# Dual_linear_VCA_chip_v1_1.net
KiCad netlist of a schematic drawn in EAGLE
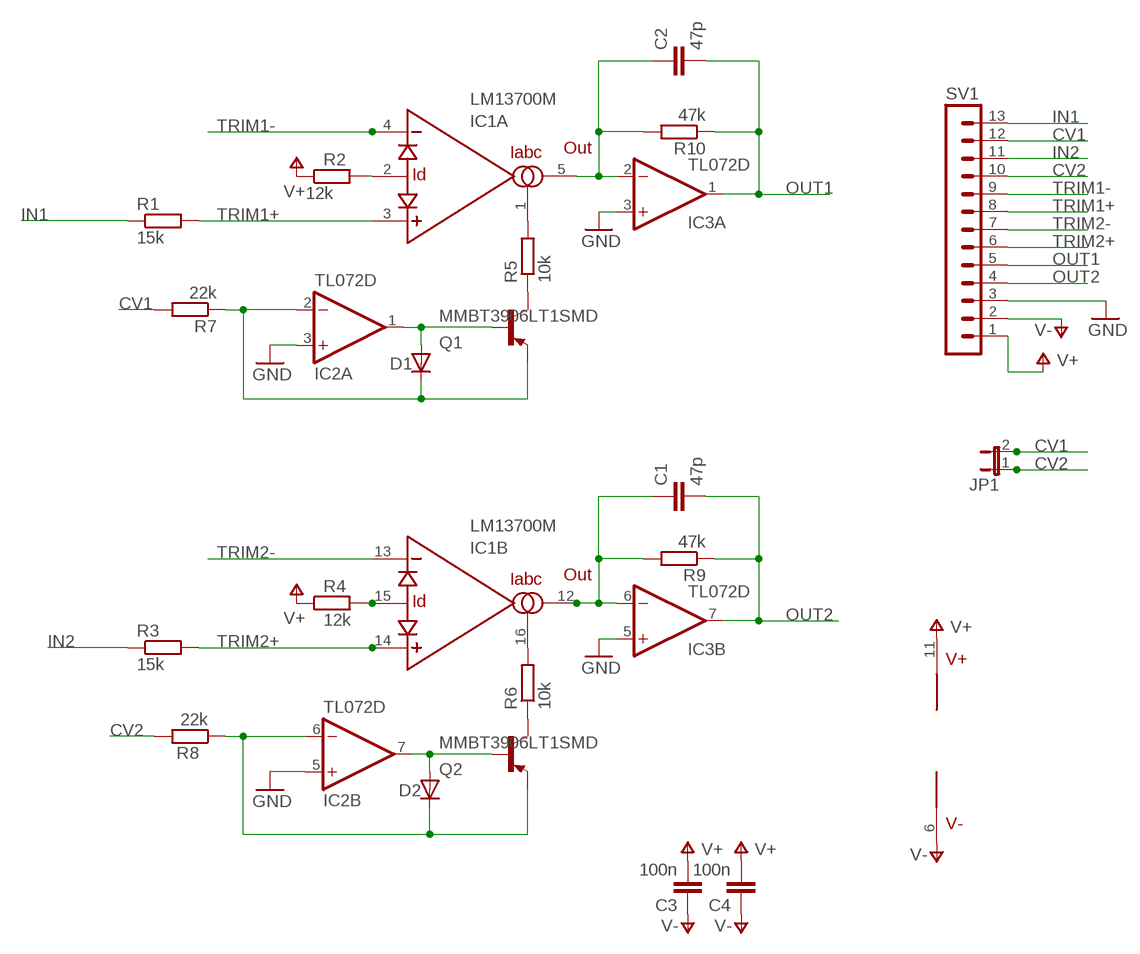
[diagram p0: schematic, sheet 1]

(export (version "E")
  (design (tool "Eeschema 10.0.6"))
  (components
    (comp (ref "C1")
      (value "47p")
      (footprint "eagle-import:C0805")
      (libsource (lib "eagle-import") (part "C-EUC0805"))
    )
    (comp (ref "C2")
      (value "47p")
      (footprint "eagle-import:C0805")
      (libsource (lib "eagle-import") (part "C-EUC0805"))
    )
    (comp (ref "C3")
      (value "100n")
      (footprint "eagle-import:C0805")
      (libsource (lib "eagle-import") (part "C-EUC0805"))
    )
    (comp (ref "C4")
      (value "100n")
      (footprint "eagle-import:C0805")
      (libsource (lib "eagle-import") (part "C-EUC0805"))
    )
    (comp (ref "D1")
      (value "DIODE-SOD80C")
      (footprint "eagle-import:SOD80C")
      (libsource (lib "eagle-import") (part "DIODE-SOD80C"))
    )
    (comp (ref "D2")
      (value "DIODE-SOD80C")
      (footprint "eagle-import:SOD80C")
      (libsource (lib "eagle-import") (part "DIODE-SOD80C"))
    )
    (comp (ref "IC1")
      (value "LM13700M")
      (footprint "eagle-import:SO16")
      (libsource (lib "eagle-import") (part "LM13700M"))
    )
    (comp (ref "IC2")
      (value "TL072D")
      (footprint "eagle-import:SO08")
      (libsource (lib "eagle-import") (part "TL072D"))
    )
    (comp (ref "IC3")
      (value "TL072D")
      (footprint "eagle-import:SO08")
      (libsource (lib "eagle-import") (part "TL072D"))
    )
    (comp (ref "JP1")
      (value "JP1E")
      (footprint "eagle-import:JP1")
      (libsource (lib "eagle-import") (part "JP1E"))
    )
    (comp (ref "Q1")
      (value "MMBT3906LT1SMD")
      (footprint "eagle-import:SOT23-BEC")
      (libsource (lib "eagle-import") (part "MMBT3906SMDLT1"))
    )
    (comp (ref "Q2")
      (value "MMBT3906LT1SMD")
      (footprint "eagle-import:SOT23-BEC")
      (libsource (lib "eagle-import") (part "MMBT3906SMDLT1"))
    )
    (comp (ref "R1")
      (value "15k")
      (footprint "eagle-import:R0805")
      (libsource (lib "eagle-import") (part "R-EU_R0805"))
    )
    (comp (ref "R2")
      (value "12k")
      (footprint "eagle-import:R0805")
      (libsource (lib "eagle-import") (part "R-EU_R0805"))
    )
    (comp (ref "R3")
      (value "15k")
      (footprint "eagle-import:R0805")
      (libsource (lib "eagle-import") (part "R-EU_R0805"))
    )
    (comp (ref "R4")
      (value "12k")
      (footprint "eagle-import:R0805")
      (libsource (lib "eagle-import") (part "R-EU_R0805"))
    )
    (comp (ref "R5")
      (value "10k")
      (footprint "eagle-import:R0805")
      (libsource (lib "eagle-import") (part "R-EU_R0805"))
    )
    (comp (ref "R6")
      (value "10k")
      (footprint "eagle-import:R0805")
      (libsource (lib "eagle-import") (part "R-EU_R0805"))
    )
    (comp (ref "R7")
      (value "22k")
      (footprint "eagle-import:R0805")
      (libsource (lib "eagle-import") (part "R-EU_R0805"))
    )
    (comp (ref "R8")
      (value "22k")
      (footprint "eagle-import:R0805")
      (libsource (lib "eagle-import") (part "R-EU_R0805"))
    )
    (comp (ref "R9")
      (value "47k")
      (footprint "eagle-import:R0805")
      (libsource (lib "eagle-import") (part "R-EU_R0805"))
    )
    (comp (ref "R10")
      (value "47k")
      (footprint "eagle-import:R0805")
      (libsource (lib "eagle-import") (part "R-EU_R0805"))
    )
    (comp (ref "SV1")
      (value "MA13-1")
      (footprint "eagle-import:MA13-1")
      (libsource (lib "eagle-import") (part "MA13-1"))
    )
  )
  (nets
    (net (code "1") (name "/CV1") (class "Default")
      (node (ref "JP1") (pin "2") (pinfunction "2_2") (pintype "passive"))
      (node (ref "R7") (pin "2") (pinfunction "2_2") (pintype "passive"))
      (node (ref "SV1") (pin "12") (pinfunction "12_12") (pintype "passive"))
    )
    (net (code "2") (name "/CV2") (class "Default")
      (node (ref "JP1") (pin "1") (pinfunction "1_1") (pintype "passive"))
      (node (ref "R8") (pin "2") (pinfunction "2_2") (pintype "passive"))
      (node (ref "SV1") (pin "10") (pinfunction "10_10") (pintype "passive"))
    )
    (net (code "3") (name "/IN1") (class "Default")
      (node (ref "R1") (pin "1") (pinfunction "1_1") (pintype "passive"))
      (node (ref "SV1") (pin "13") (pinfunction "13_13") (pintype "passive"))
    )
    (net (code "4") (name "/IN2") (class "Default")
      (node (ref "R3") (pin "1") (pinfunction "1_1") (pintype "passive"))
      (node (ref "SV1") (pin "11") (pinfunction "11_11") (pintype "passive"))
    )
    (net (code "5") (name "/OUT1") (class "Default")
      (node (ref "C2") (pin "2") (pinfunction "2_2") (pintype "passive"))
      (node (ref "IC3") (pin "1") (pinfunction "OUT_1") (pintype "output"))
      (node (ref "R10") (pin "1") (pinfunction "1_1") (pintype "passive"))
      (node (ref "SV1") (pin "5") (pinfunction "5_5") (pintype "passive"))
    )
    (net (code "6") (name "/OUT2") (class "Default")
      (node (ref "C1") (pin "2") (pinfunction "2_2") (pintype "passive"))
      (node (ref "IC3") (pin "7") (pinfunction "OUT_7") (pintype "output"))
      (node (ref "R9") (pin "1") (pinfunction "1_1") (pintype "passive"))
      (node (ref "SV1") (pin "4") (pinfunction "4_4") (pintype "passive"))
    )
    (net (code "7") (name "/TRIM1+") (class "Default")
      (node (ref "IC1") (pin "3") (pinfunction "+IN_3") (pintype "bidirectional"))
      (node (ref "R1") (pin "2") (pinfunction "2_2") (pintype "passive"))
      (node (ref "SV1") (pin "8") (pinfunction "8_8") (pintype "passive"))
    )
    (net (code "8") (name "/TRIM1-") (class "Default")
      (node (ref "IC1") (pin "4") (pinfunction "-IN_4") (pintype "bidirectional"))
      (node (ref "SV1") (pin "9") (pinfunction "9_9") (pintype "passive"))
    )
    (net (code "9") (name "/TRIM2+") (class "Default")
      (node (ref "IC1") (pin "14") (pinfunction "+IN_14") (pintype "bidirectional"))
      (node (ref "R3") (pin "2") (pinfunction "2_2") (pintype "passive"))
      (node (ref "SV1") (pin "6") (pinfunction "6_6") (pintype "passive"))
    )
    (net (code "10") (name "/TRIM2-") (class "Default")
      (node (ref "IC1") (pin "13") (pinfunction "-IN_13") (pintype "bidirectional"))
      (node (ref "SV1") (pin "7") (pinfunction "7_7") (pintype "passive"))
    )
    (net (code "11") (name "GND") (class "Default")
      (node (ref "IC2") (pin "3") (pinfunction "+IN_3") (pintype "input"))
      (node (ref "IC2") (pin "5") (pinfunction "+IN_5") (pintype "input"))
      (node (ref "IC3") (pin "3") (pinfunction "+IN_3") (pintype "input"))
      (node (ref "IC3") (pin "5") (pinfunction "+IN_5") (pintype "input"))
      (node (ref "SV1") (pin "3") (pinfunction "3_3") (pintype "passive"))
    )
    (net (code "12") (name "Net-(IC1A-IABC)") (class "Default")
      (node (ref "IC1") (pin "1") (pinfunction "IABC_1") (pintype "bidirectional"))
      (node (ref "R5") (pin "2") (pinfunction "2_2") (pintype "passive"))
    )
    (net (code "13") (name "Net-(IC1A-ID)") (class "Default")
      (node (ref "IC1") (pin "2") (pinfunction "ID_2") (pintype "bidirectional"))
      (node (ref "R2") (pin "2") (pinfunction "2_2") (pintype "passive"))
    )
    (net (code "14") (name "Net-(IC1A-OUT)") (class "Default")
      (node (ref "C2") (pin "1") (pinfunction "1_1") (pintype "passive"))
      (node (ref "IC1") (pin "5") (pinfunction "OUT_5") (pintype "bidirectional"))
      (node (ref "IC3") (pin "2") (pinfunction "-IN_2") (pintype "input"))
      (node (ref "R10") (pin "2") (pinfunction "2_2") (pintype "passive"))
    )
    (net (code "15") (name "Net-(IC1B-IABC)") (class "Default")
      (node (ref "IC1") (pin "16") (pinfunction "IABC_16") (pintype "bidirectional"))
      (node (ref "R6") (pin "2") (pinfunction "2_2") (pintype "passive"))
    )
    (net (code "16") (name "Net-(IC1B-ID)") (class "Default")
      (node (ref "IC1") (pin "15") (pinfunction "ID_15") (pintype "bidirectional"))
      (node (ref "R4") (pin "2") (pinfunction "2_2") (pintype "passive"))
    )
    (net (code "17") (name "Net-(IC1B-OUT)") (class "Default")
      (node (ref "C1") (pin "1") (pinfunction "1_1") (pintype "passive"))
      (node (ref "IC1") (pin "12") (pinfunction "OUT_12") (pintype "bidirectional"))
      (node (ref "IC3") (pin "6") (pinfunction "-IN_6") (pintype "input"))
      (node (ref "R9") (pin "2") (pinfunction "2_2") (pintype "passive"))
    )
    (net (code "18") (name "Net-(IC2A--IN)") (class "Default")
      (node (ref "D1") (pin "C") (pinfunction "C_C") (pintype "passive"))
      (node (ref "IC2") (pin "2") (pinfunction "-IN_2") (pintype "input"))
      (node (ref "Q1") (pin "E") (pinfunction "E_E") (pintype "passive"))
      (node (ref "R7") (pin "1") (pinfunction "1_1") (pintype "passive"))
    )
    (net (code "19") (name "Net-(IC2A-OUT)") (class "Default")
      (node (ref "D1") (pin "A") (pinfunction "A_A") (pintype "passive"))
      (node (ref "IC2") (pin "1") (pinfunction "OUT_1") (pintype "output"))
      (node (ref "Q1") (pin "B") (pinfunction "B_B") (pintype "passive"))
    )
    (net (code "20") (name "Net-(IC2B--IN)") (class "Default")
      (node (ref "D2") (pin "C") (pinfunction "C_C") (pintype "passive"))
      (node (ref "IC2") (pin "6") (pinfunction "-IN_6") (pintype "input"))
      (node (ref "Q2") (pin "E") (pinfunction "E_E") (pintype "passive"))
      (node (ref "R8") (pin "1") (pinfunction "1_1") (pintype "passive"))
    )
    (net (code "21") (name "Net-(IC2B-OUT)") (class "Default")
      (node (ref "D2") (pin "A") (pinfunction "A_A") (pintype "passive"))
      (node (ref "IC2") (pin "7") (pinfunction "OUT_7") (pintype "output"))
      (node (ref "Q2") (pin "B") (pinfunction "B_B") (pintype "passive"))
    )
    (net (code "22") (name "Net-(Q1-PadC)") (class "Default")
      (node (ref "Q1") (pin "C") (pinfunction "C_C") (pintype "passive"))
      (node (ref "R5") (pin "1") (pinfunction "1_1") (pintype "passive"))
    )
    (net (code "23") (name "Net-(Q2-PadC)") (class "Default")
      (node (ref "Q2") (pin "C") (pinfunction "C_C") (pintype "passive"))
      (node (ref "R6") (pin "1") (pinfunction "1_1") (pintype "passive"))
    )
    (net (code "24") (name "V+") (class "Default")
      (node (ref "C3") (pin "2") (pinfunction "2_2") (pintype "passive"))
      (node (ref "C4") (pin "2") (pinfunction "2_2") (pintype "passive"))
      (node (ref "IC1") (pin "11") (pinfunction "V+_11") (pintype "bidirectional"))
      (node (ref "R2") (pin "1") (pinfunction "1_1") (pintype "passive"))
      (node (ref "R4") (pin "1") (pinfunction "1_1") (pintype "passive"))
      (node (ref "SV1") (pin "1") (pinfunction "1_1") (pintype "passive"))
    )
    (net (code "25") (name "V-") (class "Default")
      (node (ref "C3") (pin "1") (pinfunction "1_1") (pintype "passive"))
      (node (ref "C4") (pin "1") (pinfunction "1_1") (pintype "passive"))
      (node (ref "IC1") (pin "6") (pinfunction "V-_6") (pintype "bidirectional"))
      (node (ref "SV1") (pin "2") (pinfunction "2_2") (pintype "passive"))
    )
  )
)
